# Low-Current_Power_Supply.net
KiCad netlist of a schematic drawn in Altium Designer
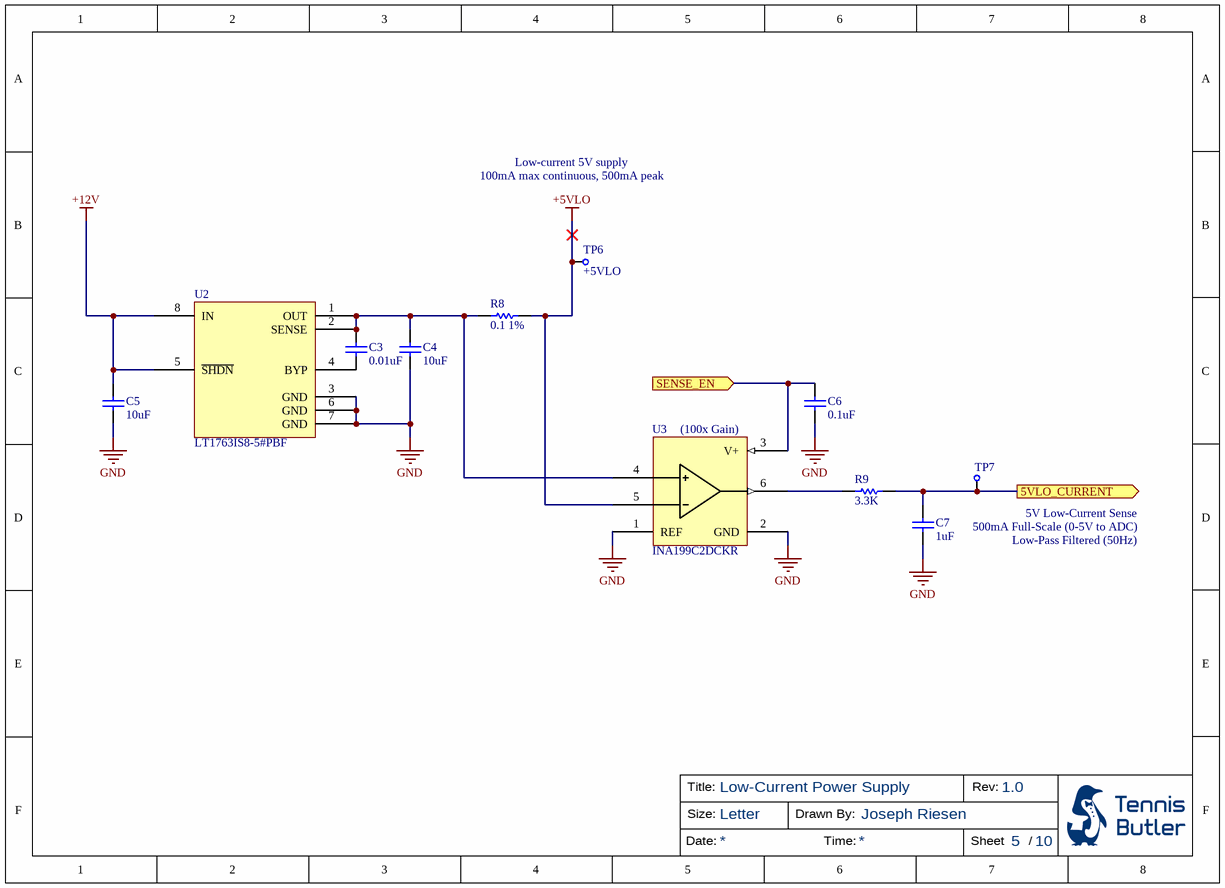
[diagram p0: Low-Current Power Supply.SchDoc]

(export (version "E")
  (design (tool "Eeschema 10.0.6"))
  (components
    (comp (ref "C3")
      (value "0.01uF")
      (footprint "CAPC1608X87X35ML15T15")
      (fields (field (name "MANUFACTURER") "Kemet") (field (name "PART NUMBER") "C0603C103J3GACTU"))
      (libsource (lib "Altium Content Vault") (part "CAP"))
    )
    (comp (ref "C4")
      (value "10uF")
      (footprint "CAPC2013X145X50ML20T25")
      (fields (field (name "MANUFACTURER") "Kemet") (field (name "PART NUMBER") "C0805C106K9PACTU"))
      (libsource (lib "Altium Content Vault") (part "CAP"))
    )
    (comp (ref "C5")
      (value "10uF")
      (footprint "CAPC2013X145X50ML20T25")
      (fields (field (name "MANUFACTURER") "Kemet") (field (name "PART NUMBER") "C0805C106K9PACTU"))
      (libsource (lib "Altium Content Vault") (part "CAP"))
    )
    (comp (ref "C6")
      (value "0.1uF")
      (footprint "CAPC0805(2012)100_M")
      (description "CAP 100nF 6.3V ±10% 0805 (2012 Metric) Thickness 1mm SMD")
      (fields (field (name "TOLERANCE") "Â±10%"))
      (libsource (lib "Altium Content Vault") (part "CAP"))
    )
    (comp (ref "C7")
      (value "1uF")
      (footprint "CAPC2013X100X50ML20T25")
      (fields (field (name "MANUFACTURER") "Kemet") (field (name "PART NUMBER") "C0805C105K9RACTU"))
      (libsource (lib "Altium Content Vault") (part "CAP"))
    )
    (comp (ref "R8")
      (value "0.1 1%")
      (footprint "RESC3216X70X50NL05T20")
      (fields (field (name "PART NUMBER") "ERJ-L08KF10CV") (field (name "MANUFACTURER") "Panasonic"))
      (libsource (lib "Altium Content Vault") (part "RES"))
    )
    (comp (ref "R9")
      (value "3.3K")
      (footprint "RESC2013X70X40ML20T20")
      (description "RES SMD 3.3K OHM 1% 1/8W 0805")
      (fields (field (name "MANUFACTURER") "Panasonic") (field (name "PART NUMBER") "ERJ6ENF3301V"))
      (libsource (lib "Altium Content Vault") (part "RES"))
    )
    (comp (ref "TP6")
      (value "+5VLO")
      (footprint "Test Point")
      (libsource (lib "Miscellaneous") (part "Test Point"))
    )
    (comp (ref "TP7")
      (value "5VLO CSENSE")
      (footprint "Test Point")
      (libsource (lib "Miscellaneous") (part "Test Point"))
    )
    (comp (ref "U2")
      (value "LT1763IS8-5#PBF")
      (footprint "SOIC127P600X175-8M")
      (description "IC REG LINEAR 5V 500MA 8SOIC")
      (fields (field (name "MANUFACTURER") "Analog Devices / Linear Technology"))
      (libsource (lib "LT1763") (part "LT1763IS8-5#PBF"))
    )
    (comp (ref "U3")
      (value "INA199C2DCKR")
      (footprint "TSOP65P240X110-6M")
      (description "IC OP AMP CURR SENSE SC70-6")
      (fields (field (name "MANUFACTURER") "Texas Instruments"))
      (libsource (lib "INA199") (part "INA199C2DCKR"))
    )
  )
  (nets
    (net (code "1") (name "+5VLO") (class "Default")
      (node (ref "R8") (pin "2") (pinfunction "2_2") (pintype "passive"))
      (node (ref "TP6") (pin "1") (pinfunction "1_1") (pintype "passive"))
      (node (ref "U3") (pin "5") (pinfunction "IN-_5") (pintype "passive"))
    )
    (net (code "2") (name "+12V") (class "Default")
      (node (ref "C5") (pin "2") (pinfunction "2_2") (pintype "passive"))
      (node (ref "U2") (pin "5") (pinfunction "~{SHDN}_5") (pintype "passive"))
      (node (ref "U2") (pin "8") (pinfunction "IN_8") (pintype "passive"))
    )
    (net (code "3") (name "/5VLO_CURRENT") (class "Default")
      (node (ref "C7") (pin "2") (pinfunction "2_2") (pintype "passive"))
      (node (ref "R9") (pin "2") (pinfunction "2_2") (pintype "passive"))
      (node (ref "TP7") (pin "1") (pinfunction "1_1") (pintype "passive"))
    )
    (net (code "4") (name "/SENSE_EN") (class "Default")
      (node (ref "C6") (pin "2") (pinfunction "2_2") (pintype "passive"))
      (node (ref "U3") (pin "3") (pinfunction "V+_3") (pintype "input"))
    )
    (net (code "5") (name "GND") (class "Default")
      (node (ref "C4") (pin "1") (pinfunction "1_1") (pintype "passive"))
      (node (ref "C5") (pin "1") (pinfunction "1_1") (pintype "passive"))
      (node (ref "C6") (pin "1") (pinfunction "1_1") (pintype "passive"))
      (node (ref "C7") (pin "1") (pinfunction "1_1") (pintype "passive"))
      (node (ref "U2") (pin "3") (pinfunction "GND_3") (pintype "power_in"))
      (node (ref "U2") (pin "6") (pinfunction "GND_6") (pintype "power_in"))
      (node (ref "U2") (pin "7") (pinfunction "GND_7") (pintype "power_in"))
      (node (ref "U3") (pin "1") (pinfunction "REF_1") (pintype "passive"))
      (node (ref "U3") (pin "2") (pinfunction "GND_2") (pintype "power_in"))
    )
    (net (code "6") (name "Net-(U2-BYP)") (class "Default")
      (node (ref "C3") (pin "1") (pinfunction "1_1") (pintype "passive"))
      (node (ref "U2") (pin "4") (pinfunction "BYP_4") (pintype "passive"))
    )
    (net (code "7") (name "Net-(U2-OUT)") (class "Default")
      (node (ref "C3") (pin "2") (pinfunction "2_2") (pintype "passive"))
      (node (ref "C4") (pin "2") (pinfunction "2_2") (pintype "passive"))
      (node (ref "R8") (pin "1") (pinfunction "1_1") (pintype "passive"))
      (node (ref "U2") (pin "1") (pinfunction "OUT_1") (pintype "power_in"))
      (node (ref "U2") (pin "2") (pinfunction "SENSE_2") (pintype "passive"))
      (node (ref "U3") (pin "4") (pinfunction "IN+_4") (pintype "passive"))
    )
    (net (code "8") (name "Net-(U3-OUT)") (class "Default")
      (node (ref "R9") (pin "1") (pinfunction "1_1") (pintype "passive"))
      (node (ref "U3") (pin "6") (pinfunction "OUT_6") (pintype "output"))
    )
  )
)
